# SH2_-_POWER.net
KiCad netlist of a schematic drawn in Altium Designer
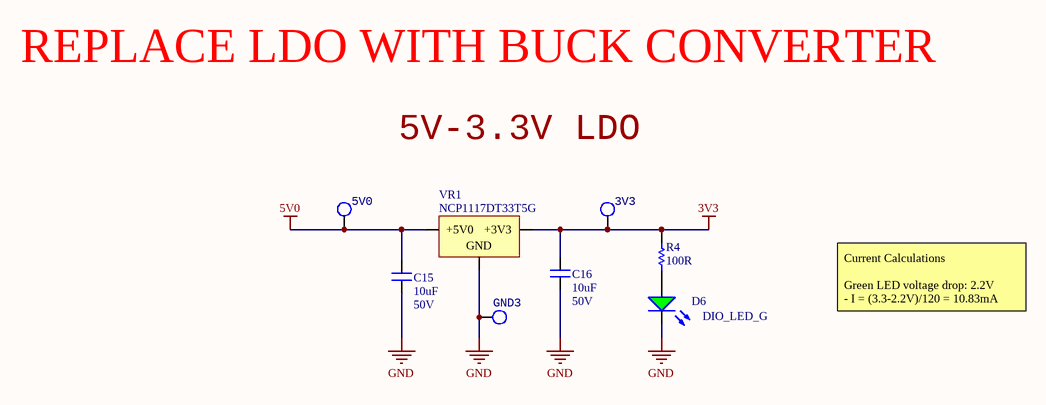
[diagram p0: SH2 - POWER.SchDoc]

(export (version "E")
  (design (tool "Eeschema 10.0.6"))
  (components
    (comp (ref "3V3")
      (value "TESTPOINT_LOOP")
      (footprint "TESTPOINT_LOOP")
      (description "Loop testpoint through-hole pad")
      (fields (field (name "MANUFACTURER") "Keystone Electronics"))
      (libsource (lib "UWRT_Schematic_Library_2020") (part "TESTPOINT_LOOP"))
    )
    (comp (ref "5V0")
      (value "TESTPOINT_LOOP")
      (footprint "TESTPOINT_LOOP")
      (description "Loop testpoint through-hole pad")
      (fields (field (name "MANUFACTURER") "Keystone Electronics"))
      (libsource (lib "UWRT_Schematic_Library_2020") (part "TESTPOINT_LOOP"))
    )
    (comp (ref "C15")
      (value "10uF")
      (footprint "CAPC1206(3216)")
      (description "CAP CER 10UF 50V X5R 1206")
      (fields
        (field (name "MPN") "GRT31CR61H106KE01L")
        (field (name "MANUFACTURER") "Murata")
        (field (name "VOLTAGE RATING") "50V")
      )
      (libsource (lib "UWRT_Schematic_Library_2020") (part "CAP_10uF_50V_1206"))
    )
    (comp (ref "C16")
      (value "10uF")
      (footprint "CAPC1206(3216)")
      (description "CAP CER 10UF 50V X5R 1206")
      (fields
        (field (name "MPN") "GRT31CR61H106KE01L")
        (field (name "MANUFACTURER") "Murata")
        (field (name "VOLTAGE RATING") "50V")
      )
      (libsource (lib "UWRT_Schematic_Library_2020") (part "CAP_10uF_50V_1206"))
    )
    (comp (ref "D6")
      (value "DIO_LED_G")
      (footprint "LED_0805_LINE")
      (description "LED GREEN DIFFUSED 0805 SMD")
      (fields (field (name "MPN") "LG R971-KN-1") (field (name "MANUFACTURER") "OSRAM"))
      (libsource (lib "UWRT_Schematic_Library_2020") (part "DIO_LED_G"))
    )
    (comp (ref "GND3")
      (value "TESTPOINT_LOOP")
      (footprint "TESTPOINT_LOOP")
      (description "Loop testpoint through-hole pad")
      (fields (field (name "MANUFACTURER") "Keystone Electronics"))
      (libsource (lib "UWRT_Schematic_Library_2020") (part "TESTPOINT_LOOP"))
    )
    (comp (ref "R4")
      (value "100R")
      (footprint "RESC0603(1608)_N")
      (description "RES SMD 100 OHM 1% 1/10W 0603")
      (fields (field (name "MANUFACTURER") "Yageo") (field (name "MPN") "RC0603FR-07100RL"))
      (libsource (lib "UWRT_Schematic_Library_2020") (part "RES_100R_0603"))
    )
    (comp (ref "VR1")
      (value "5V0_3V3_LDO")
      (footprint "VOLTAGE_REGULATOR")
      (description "IC REG LINEAR 3.3V 1A DPAK")
      (fields (field (name "MPN") "NCP1117DT33T5G") (field (name "MANUFACTURER") "ON Semiconductor"))
      (libsource (lib "UWRT_Schematic_Library_2020") (part "5V0_3V3_LDO"))
    )
  )
  (nets
    (net (code "1") (name "3V3") (class "Default")
      (node (ref "3V3") (pin "1") (pintype "passive"))
      (node (ref "C16") (pin "1") (pinfunction "1_1") (pintype "passive"))
      (node (ref "R4") (pin "2") (pinfunction "2_2") (pintype "passive"))
      (node (ref "VR1") (pin "2") (pinfunction "+3V3_2") (pintype "passive"))
    )
    (net (code "2") (name "5V0") (class "Default")
      (node (ref "5V0") (pin "1") (pintype "passive"))
      (node (ref "C15") (pin "1") (pinfunction "1_1") (pintype "passive"))
      (node (ref "VR1") (pin "3") (pinfunction "+5V0_3") (pintype "passive"))
    )
    (net (code "3") (name "GND") (class "Default")
      (node (ref "C15") (pin "2") (pinfunction "2_2") (pintype "passive"))
      (node (ref "C16") (pin "2") (pinfunction "2_2") (pintype "passive"))
      (node (ref "D6") (pin "2") (pinfunction "K_2") (pintype "passive"))
      (node (ref "GND3") (pin "1") (pintype "passive"))
      (node (ref "VR1") (pin "1") (pinfunction "GND_1") (pintype "passive"))
    )
    (net (code "4") (name "Net-(D6-A)") (class "Default")
      (node (ref "D6") (pin "1") (pinfunction "A_1") (pintype "passive"))
      (node (ref "R4") (pin "1") (pinfunction "1_1") (pintype "passive"))
    )
  )
)
